# Charger_group2.net
KiCad netlist of a schematic drawn in Altium Designer
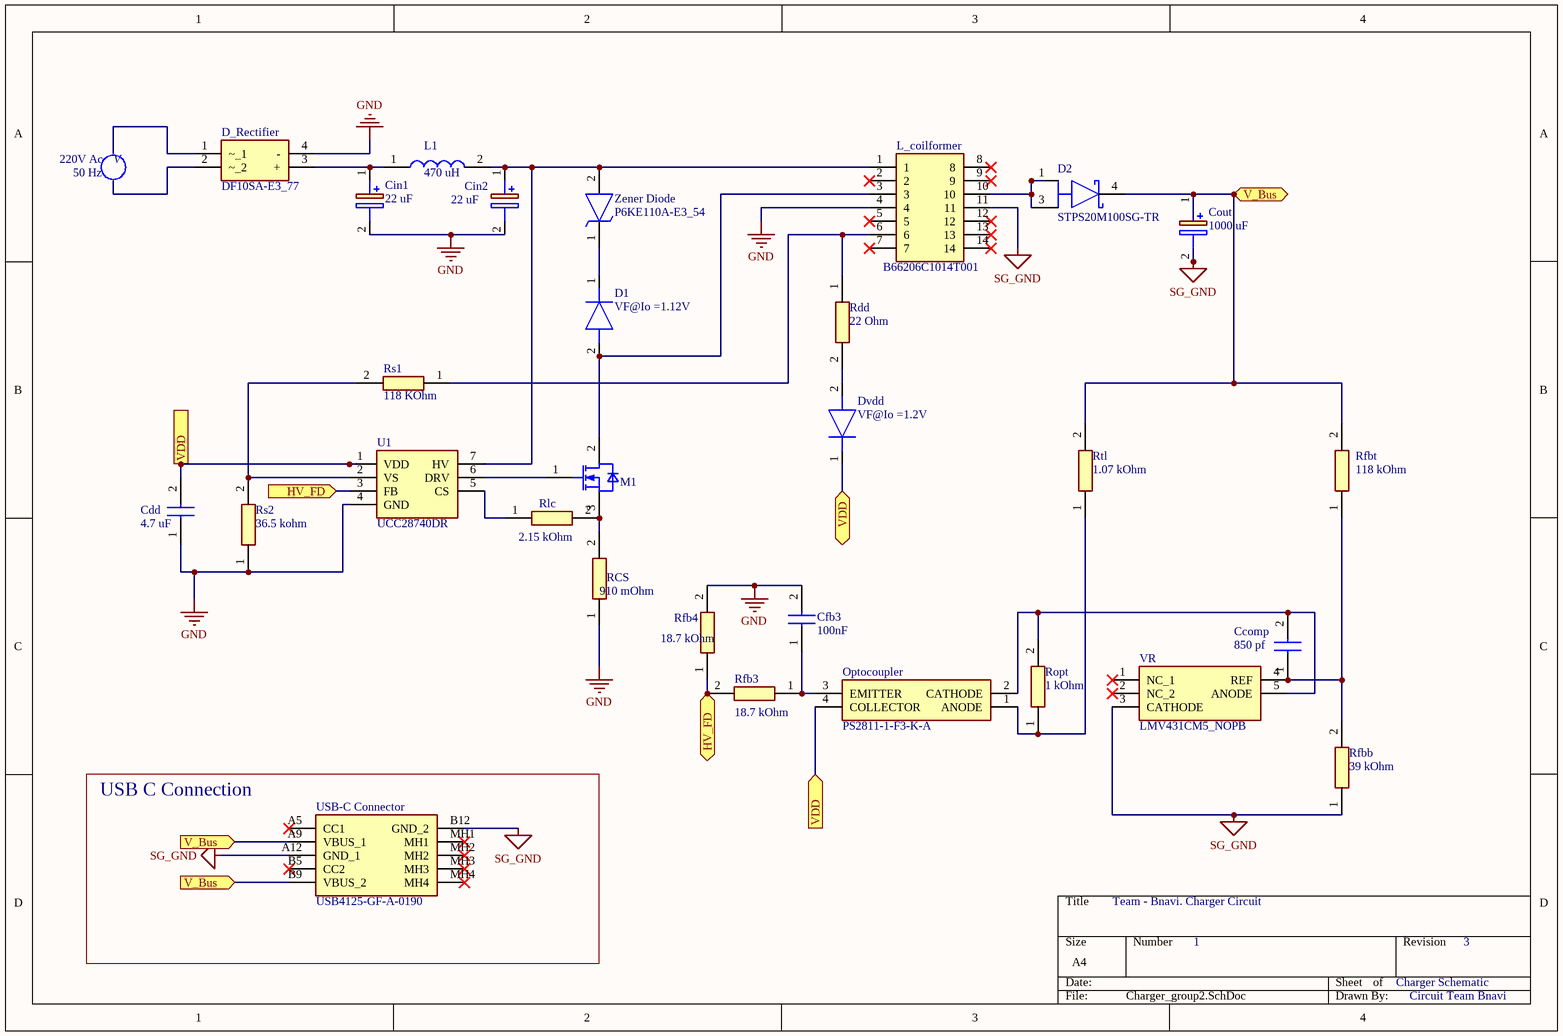
[diagram p0: Charger_group2.SchDoc]

(export (version "E")
  (design (tool "Eeschema 10.0.6"))
  (components
    (comp (ref "Ccomp")
      (value "850 pf")
      (footprint "SamacSys:CAPC1608X90N")
      (description "Capacitor")
      (fields
        (field (name "MANUFACTURER_PART_NUMBER") "06031C851JAT2A")
        (field (name "MOUSER PART NUMBER") "581-06031C851JAT2A")
      )
      (libsource (lib "SamacSys") (part "06031C851JAT2A"))
    )
    (comp (ref "Cdd")
      (value "4.7 uF")
      (footprint "SamacSys:CAPC2012X145N")
      (description "Capacitor")
      (fields
        (field (name "MANUFACTURER_PART_NUMBER") "CGA4J1X7R1V475K125AC")
        (field (name "MOUSER PART NUMBER") "810-CGA4J1X7R1V475KC")
      )
      (libsource (lib "*") (part "CGA4J1X7R1V475K125AC"))
    )
    (comp (ref "Cfb3")
      (value "100nF")
      (footprint "SamacSys:CAPC2013X94N")
      (description "Capacitor")
      (fields
        (field (name "MANUFACTURER_PART_NUMBER") "08053C104JAZ2A")
        (field (name "MOUSER PART NUMBER") "581-08053C104JAZ2A")
      )
      (libsource (lib "SamacSys") (part "08053C104JAZ2A"))
    )
    (comp (ref "Cin1")
      (value "22 uF")
      (footprint "SamacSys:CAPPRD500W60D1275H2200")
      (description "Capacitor Polarised")
      (fields
        (field (name "MANUFACTURER_PART_NUMBER") "400PK22MEFC12.5X20")
        (field (name "MOUSER PART NUMBER") "232-400PK22MEFC125X2")
      )
      (libsource (lib "SamacSys") (part "400PK22MEFC12.5X20"))
    )
    (comp (ref "Cin2")
      (value "22 uF")
      (footprint "SamacSys:CAPPRD500W60D1275H2200")
      (description "Capacitor Polarised")
      (fields
        (field (name "MANUFACTURER_PART_NUMBER") "400PK22MEFC12.5X20")
        (field (name "MOUSER PART NUMBER") "232-400PK22MEFC125X2")
      )
      (libsource (lib "SamacSys") (part "400PK22MEFC12.5X20"))
    )
    (comp (ref "Cout")
      (value "1000 uF")
      (footprint "SamacSys:CAPPRD500W65D1000H2700")
      (description "Capacitor Polarised")
      (fields
        (field (name "MANUFACTURER_PART_NUMBER") "EEU-FC1C102")
        (field (name "MOUSER PART NUMBER") "667-EEU-FC1C102")
      )
      (libsource (lib "*") (part "EEU-FC1C102"))
    )
    (comp (ref "D1")
      (value "VF@Io =1.12V")
      (footprint "SamacSys:DIOM7959X262N")
      (description "Diode")
      (fields
        (field (name "MANUFACTURER_PART_NUMBER") "CD214C-F3600")
        (field (name "MOUSER PART NUMBER") "652-CD214C-F3600")
      )
      (libsource (lib "SamacSys") (part "CD214C-F3600"))
    )
    (comp (ref "D2")
      (value "STPS20M100SG-TR")
      (footprint "FP-STPS20M100SG-TR-MFG")
      (description "DIODE SCHOTTKY 100V 20A D2PAK")
      (fields
        (field (name "MANUFACTURER") "STMicroelectronics")
        (field (name "OCTOPART") "https://octopart.com/stps20m100sg-tr-stmicroelectronics-17669033")
      )
      (libsource (lib "Altium Content Vault") (part "51e2ec8066ff851c79fc2400fdb0e37"))
    )
    (comp (ref "Dvdd")
      (value "VF@Io =1.2V")
      (footprint "SamacSys:DIOM5436X330N")
      (description "Diode")
      (fields
        (field (name "MANUFACTURER_PART_NUMBER") "UFS180Je3/TR13")
        (field (name "MOUSER PART NUMBER") "494-UFS180JE3/TR13")
      )
      (libsource (lib "SamacSys") (part "UFS180Je3_TR13"))
    )
    (comp (ref "D_Rectifier")
      (value "DF10SA-E3_77")
      (footprint "SamacSys:SOP510P1005X330-4N")
      (description "Diode")
      (fields
        (field (name "MANUFACTURER_PART_NUMBER") "DF10SA-E3/77")
        (field (name "MOUSER PART NUMBER") "625-DF10SA-E3")
      )
      (libsource (lib "SamacSys") (part "DF10SA-E3_77"))
    )
    (comp (ref "L1")
      (value "470 uH")
      (footprint "SamacSys:WE-PD2_105455")
      (description "Inductor")
      (fields
        (field (name "MANUFACTURER_PART_NUMBER") "744776247")
        (field (name "MOUSER PART NUMBER") "710-744776247")
      )
      (libsource (lib "SamacSys") (part "744776247"))
    )
    (comp (ref "L_coilformer")
      (value "B66206C1014T001")
      (footprint "SamacSys:B66206C1014T001")
      (description "Inductor")
      (libsource (lib "SamacSys") (part "B66206C1014T001"))
    )
    (comp (ref "M1")
      (value "IPD80R1K0CE")
      (footprint "TO229P994X241-3N:TO229P994X241-3N")
      (description "CoolMos CE 800V Power Transistor")
      (fields (field (name "MANUFACTURER") "Infineon Technologies"))
      (libsource (lib "IPD80R1K0CE") (part "IPD80R1K0CE"))
    )
    (comp (ref "Optocoupler")
      (value "PS2811-1-F3-K-A")
      (footprint "SamacSys:SOIC127P700X210-4N")
      (description "Integrated Circuit")
      (fields (field (name "MOUSER PART NUMBER") "551-PS2811-1-F3-K-A"))
      (libsource (lib "SamacSys") (part "PS2811-1-F3-K-A"))
    )
    (comp (ref "RCS")
      (value "910 mOhm")
      (footprint "SamacSys:RESC2012X60N")
      (description "Resistor")
      (fields
        (field (name "MANUFACTURER_PART_NUMBER") "CRM0805-FX-R910ELF")
        (field (name "MOUSER PART NUMBER") "652-CRM0805FXR910ELF")
      )
      (libsource (lib "SamacSys") (part "CRM0805-FX-R910ELF"))
    )
    (comp (ref "Rdd")
      (value "22 Ohm")
      (footprint "SamacSys:RESC1608X55N")
      (description "Resistor")
      (fields
        (field (name "MANUFACTURER_PART_NUMBER") "RC0603FR-0722RL")
        (field (name "MOUSER PART NUMBER") "603-RC0603FR-0722RL")
      )
      (libsource (lib "SamacSys") (part "RC0603FR-0722RL"))
    )
    (comp (ref "Rfb3")
      (value "18.7 kOhm")
      (footprint "SamacSys:RESC0603X26N")
      (description "Resistor")
      (fields
        (field (name "MANUFACTURER_PART_NUMBER") "RC0201FR-07205KL")
        (field (name "MOUSER PART NUMBER") "603-RC0201FR-07205KL")
      )
      (libsource (lib "SamacSys") (part "RC0201FR-07205KL"))
    )
    (comp (ref "Rfb4")
      (value "18.7 kOhm")
      (footprint "SamacSys:RESC0603X26N")
      (description "Resistor")
      (fields
        (field (name "MANUFACTURER_PART_NUMBER") "RC0201FR-0718K7L")
        (field (name "MOUSER PART NUMBER") "603-RC0201FR-0718K7L")
      )
      (libsource (lib "SamacSys") (part "RC0201FR-0718K7L"))
    )
    (comp (ref "Rfbb")
      (value "39 kOhm")
      (footprint "SamacSys:RESC1608X55N")
      (description "Resistor")
      (fields
        (field (name "MANUFACTURER_PART_NUMBER") "RC0603FR-0739KL")
        (field (name "MOUSER PART NUMBER") "603-RC0603FR-0739KL")
      )
      (libsource (lib "SamacSys") (part "RC0603FR-0739KL"))
    )
    (comp (ref "Rfbt")
      (value "118 kOhm")
      (footprint "SamacSys:RESC1005X40N")
      (description "Resistor")
      (fields
        (field (name "MANUFACTURER_PART_NUMBER") "CRCW0402118KFKED")
        (field (name "MOUSER PART NUMBER") "71-CRCW0402-118K-E3")
      )
      (libsource (lib "") (part "CRCW0402118KFKED_1"))
    )
    (comp (ref "Rlc")
      (value "2.15 kOhm")
      (footprint "SamacSys:RESC1005X40N")
      (description "Resistor")
      (fields
        (field (name "MANUFACTURER_PART_NUMBER") "CRCW04022K15FKED")
        (field (name "MOUSER PART NUMBER") "71-CRCW0402-2.15K-E3")
      )
      (libsource (lib "SamacSys") (part "CRCW04022K15FKED"))
    )
    (comp (ref "Ropt")
      (value "1 kOhm")
      (footprint "SamacSys:RESC1005X40N")
      (description "Resistor")
      (fields
        (field (name "MANUFACTURER_PART_NUMBER") "CRCW04021K00FKEDHP")
        (field (name "MOUSER PART NUMBER") "71-CRCW04021K00FKEDH")
      )
      (libsource (lib "SamacSys") (part "CRCW04021K00FKEDHP"))
    )
    (comp (ref "Rs1")
      (value "118 KOhm")
      (footprint "SamacSys:RESC1005X40N")
      (description "Resistor")
      (fields
        (field (name "MANUFACTURER_PART_NUMBER") "CRCW0402118KFKED")
        (field (name "MOUSER PART NUMBER") "71-CRCW0402-118K-E3")
      )
      (libsource (lib "SamacSys") (part "CRCW0402118KFKED"))
    )
    (comp (ref "Rs2")
      (value "36.5 kohm")
      (footprint "SamacSys:RESC0603X26N")
      (description "Resistor")
      (fields
        (field (name "MANUFACTURER_PART_NUMBER") "RC0201FR-0736K5L")
        (field (name "MOUSER PART NUMBER") "603-RC0201FR-0736K5L")
      )
      (libsource (lib "SamacSys") (part "RC0201FR-0736K5L"))
    )
    (comp (ref "Rtl")
      (value "1.07 kOhm")
      (footprint "SamacSys:RESC1005X40N")
      (description "Resistor")
      (fields
        (field (name "MANUFACTURER_PART_NUMBER") "CRCW04021K07FKED")
        (field (name "MOUSER PART NUMBER") "71-CRCW0402-1.07K-E3")
      )
      (libsource (lib "SamacSys") (part "CRCW04021K07FKED"))
    )
    (comp (ref "U1")
      (value "UCC28740DR")
      (footprint "SamacSys:D(R-PDSO-G7)")
      (description "Inductor")
      (fields (field (name "MOUSER PART NUMBER") "595-UCC28740DR"))
      (libsource (lib "SamacSys") (part "UCC28740DR"))
    )
    (comp (ref "USB-C Connector")
      (value "USB4125-GF-A-0190")
      (footprint "SamacSys:USB4125GFA0190")
      (description "Connector")
      (fields (field (name "MOUSER PART NUMBER") "640-USB4125-GF-A-190"))
      (libsource (lib "*") (part "USB4125-GF-A-0190"))
    )
    (comp (ref "VR")
      (value "LMV431CM5_NOPB")
      (footprint "SamacSys:SOT95P280X145-5N")
      (description "Integrated Circuit")
      (fields
        (field (name "MANUFACTURER_PART_NUMBER") "LMV431CM5/NOPB")
        (field (name "MOUSER PART NUMBER") "926-LMV431CM5/NOPB")
      )
      (libsource (lib "SamacSys") (part "LMV431CM5_NOPB"))
    )
    (comp (ref "Zener Diode")
      (value "P6KE110A-E3_54")
      (footprint "SamacSys:DIOAD1995W86L635D340")
      (description "TVS Diode (Uni-directional)")
      (fields
        (field (name "MANUFACTURER_PART_NUMBER") "P6KE110A-E3/54")
        (field (name "MOUSER PART NUMBER") "625-P6KE110A-E3")
      )
      (libsource (lib "SamacSys") (part "P6KE110A-E3_54"))
    )
  )
  (nets
    (net (code "1") (name "/HV_FD") (class "Default")
      (node (ref "Rfb3") (pin "2") (pinfunction "2_2") (pintype "passive"))
      (node (ref "Rfb4") (pin "1") (pinfunction "1_1") (pintype "passive"))
      (node (ref "U1") (pin "3") (pinfunction "FB_3") (pintype "passive"))
    )
    (net (code "2") (name "/VDD") (class "Default")
      (node (ref "Cdd") (pin "2") (pinfunction "2_2") (pintype "passive"))
      (node (ref "Dvdd") (pin "1") (pinfunction "K_1") (pintype "passive"))
      (node (ref "Optocoupler") (pin "4") (pinfunction "COLLECTOR_4") (pintype "passive"))
      (node (ref "U1") (pin "1") (pinfunction "VDD_1") (pintype "passive"))
    )
    (net (code "3") (name "/V_Bus") (class "Default")
      (node (ref "Cout") (pin "1") (pinfunction "+_1") (pintype "passive"))
      (node (ref "D2") (pin "4") (pinfunction "K_4") (pintype "passive"))
      (node (ref "Rfbt") (pin "2") (pinfunction "2_2") (pintype "passive"))
      (node (ref "Rtl") (pin "2") (pinfunction "2_2") (pintype "passive"))
      (node (ref "USB-C Connector") (pin "A9") (pinfunction "VBUS_1_A9") (pintype "passive"))
      (node (ref "USB-C Connector") (pin "B9") (pinfunction "VBUS_2_B9") (pintype "passive"))
    )
    (net (code "4") (name "GND") (class "Default")
      (node (ref "Cdd") (pin "1") (pinfunction "1_1") (pintype "passive"))
      (node (ref "Cfb3") (pin "2") (pinfunction "C2_2") (pintype "passive"))
      (node (ref "Cin1") (pin "2") (pinfunction "-_2") (pintype "passive"))
      (node (ref "Cin2") (pin "2") (pinfunction "-_2") (pintype "passive"))
      (node (ref "D_Rectifier") (pin "4") (pinfunction "-_4") (pintype "passive"))
      (node (ref "L_coilformer") (pin "4") (pinfunction "4_4") (pintype "passive"))
      (node (ref "RCS") (pin "1") (pinfunction "1_1") (pintype "passive"))
      (node (ref "Rfb4") (pin "2") (pinfunction "2_2") (pintype "passive"))
      (node (ref "Rs2") (pin "1") (pinfunction "1_1") (pintype "passive"))
      (node (ref "U1") (pin "4") (pinfunction "GND_4") (pintype "passive"))
    )
    (net (code "5") (name "Net-(Cfb3-C1)") (class "Default")
      (node (ref "Cfb3") (pin "1") (pinfunction "C1_1") (pintype "passive"))
      (node (ref "Optocoupler") (pin "3") (pinfunction "EMITTER_3") (pintype "passive"))
      (node (ref "Rfb3") (pin "1") (pinfunction "1_1") (pintype "passive"))
    )
    (net (code "6") (name "Net-(Cin1-+)") (class "Default")
      (node (ref "Cin1") (pin "1") (pinfunction "+_1") (pintype "passive"))
      (node (ref "D_Rectifier") (pin "3") (pinfunction "+_3") (pintype "passive"))
      (node (ref "L1") (pin "1") (pinfunction "1_1") (pintype "passive"))
    )
    (net (code "7") (name "Net-(Cin2-+)") (class "Default")
      (node (ref "Cin2") (pin "1") (pinfunction "+_1") (pintype "passive"))
      (node (ref "L1") (pin "2") (pinfunction "2_2") (pintype "passive"))
      (node (ref "L_coilformer") (pin "1") (pinfunction "1_1") (pintype "passive"))
      (node (ref "U1") (pin "7") (pinfunction "HV_7") (pintype "passive"))
      (node (ref "Zener Diode") (pin "2") (pinfunction "A_2") (pintype "passive"))
    )
    (net (code "8") (name "Net-(D1-A)") (class "Default")
      (node (ref "D1") (pin "2") (pinfunction "A_2") (pintype "passive"))
      (node (ref "L_coilformer") (pin "3") (pinfunction "3_3") (pintype "passive"))
      (node (ref "M1") (pin "2") (pinfunction "DRAIN_2") (pintype "passive"))
    )
    (net (code "9") (name "Net-(D1-K)") (class "Default")
      (node (ref "D1") (pin "1") (pinfunction "K_1") (pintype "passive"))
      (node (ref "Zener Diode") (pin "1") (pinfunction "K_1") (pintype "passive"))
    )
    (net (code "10") (name "Net-(D2-A-Pad1)") (class "Default")
      (node (ref "D2") (pin "1") (pinfunction "A_1") (pintype "passive"))
      (node (ref "D2") (pin "3") (pinfunction "A_3") (pintype "passive"))
      (node (ref "L_coilformer") (pin "10") (pinfunction "10_10") (pintype "passive"))
    )
    (net (code "11") (name "Net-(Dvdd-A)") (class "Default")
      (node (ref "Dvdd") (pin "2") (pinfunction "A_2") (pintype "passive"))
      (node (ref "Rdd") (pin "2") (pinfunction "2_2") (pintype "passive"))
    )
    (net (code "12") (name "Net-(L_coilformer-Pad6)") (class "Default")
      (node (ref "L_coilformer") (pin "6") (pinfunction "6_6") (pintype "passive"))
      (node (ref "Rdd") (pin "1") (pinfunction "1_1") (pintype "passive"))
      (node (ref "Rs1") (pin "1") (pinfunction "1_1") (pintype "passive"))
    )
    (net (code "13") (name "Net-(M1-GATE)") (class "Default")
      (node (ref "M1") (pin "1") (pinfunction "GATE_1") (pintype "passive"))
      (node (ref "U1") (pin "6") (pinfunction "DRV_6") (pintype "passive"))
    )
    (net (code "14") (name "Net-(M1-SOURCE)") (class "Default")
      (node (ref "M1") (pin "3") (pinfunction "SOURCE_3") (pintype "passive"))
      (node (ref "RCS") (pin "2") (pinfunction "2_2") (pintype "passive"))
      (node (ref "Rlc") (pin "2") (pinfunction "2_2") (pintype "passive"))
    )
    (net (code "15") (name "Net-(Optocoupler-ANODE)") (class "Default")
      (node (ref "Optocoupler") (pin "1") (pinfunction "ANODE_1") (pintype "passive"))
      (node (ref "Ropt") (pin "1") (pinfunction "1_1") (pintype "passive"))
      (node (ref "Rtl") (pin "1") (pinfunction "1_1") (pintype "passive"))
    )
    (net (code "16") (name "Net-(Optocoupler-CATHODE)") (class "Default")
      (node (ref "Ccomp") (pin "2") (pinfunction "2_2") (pintype "passive"))
      (node (ref "Optocoupler") (pin "2") (pinfunction "CATHODE_2") (pintype "passive"))
      (node (ref "Ropt") (pin "2") (pinfunction "2_2") (pintype "passive"))
      (node (ref "VR") (pin "5") (pinfunction "ANODE_5") (pintype "passive"))
    )
    (net (code "17") (name "Net-(U1-CS)") (class "Default")
      (node (ref "Rlc") (pin "1") (pinfunction "1_1") (pintype "passive"))
      (node (ref "U1") (pin "5") (pinfunction "CS_5") (pintype "passive"))
    )
    (net (code "18") (name "Net-(U1-VS)") (class "Default")
      (node (ref "Rs1") (pin "2") (pinfunction "2_2") (pintype "passive"))
      (node (ref "Rs2") (pin "2") (pinfunction "2_2") (pintype "passive"))
      (node (ref "U1") (pin "2") (pinfunction "VS_2") (pintype "passive"))
    )
    (net (code "19") (name "Net-(VR-REF)") (class "Default")
      (node (ref "Ccomp") (pin "1") (pinfunction "1_1") (pintype "passive"))
      (node (ref "Rfbb") (pin "2") (pinfunction "2_2") (pintype "passive"))
      (node (ref "Rfbt") (pin "1") (pinfunction "1_1") (pintype "passive"))
      (node (ref "VR") (pin "4") (pinfunction "REF_4") (pintype "passive"))
    )
    (net (code "20") (name "SG_GND") (class "Default")
      (node (ref "Cout") (pin "2") (pinfunction "-_2") (pintype "passive"))
      (node (ref "L_coilformer") (pin "11") (pinfunction "11_11") (pintype "passive"))
      (node (ref "Rfbb") (pin "1") (pinfunction "1_1") (pintype "passive"))
      (node (ref "USB-C Connector") (pin "A12") (pinfunction "GND_1_A12") (pintype "passive"))
      (node (ref "USB-C Connector") (pin "B12") (pinfunction "GND_2_B12") (pintype "passive"))
      (node (ref "VR") (pin "3") (pinfunction "CATHODE_3") (pintype "passive"))
    )
    (net (code "21") (name "unconnected-(D_Rectifier-~_1-Pad1)") (class "Default")
      (node (ref "D_Rectifier") (pin "1") (pinfunction "~_1_1") (pintype "passive"))
    )
    (net (code "22") (name "unconnected-(D_Rectifier-~_2-Pad2)") (class "Default")
      (node (ref "D_Rectifier") (pin "2") (pinfunction "~_2_2") (pintype "passive"))
    )
    (net (code "23") (name "unconnected-(L_coilformer-Pad2)") (class "Default")
      (node (ref "L_coilformer") (pin "2") (pinfunction "2_2") (pintype "passive+no_connect"))
    )
    (net (code "24") (name "unconnected-(L_coilformer-Pad5)") (class "Default")
      (node (ref "L_coilformer") (pin "5") (pinfunction "5_5") (pintype "passive+no_connect"))
    )
    (net (code "25") (name "unconnected-(L_coilformer-Pad7)") (class "Default")
      (node (ref "L_coilformer") (pin "7") (pinfunction "7_7") (pintype "passive+no_connect"))
    )
    (net (code "26") (name "unconnected-(L_coilformer-Pad8)") (class "Default")
      (node (ref "L_coilformer") (pin "8") (pinfunction "8_8") (pintype "passive+no_connect"))
    )
    (net (code "27") (name "unconnected-(L_coilformer-Pad9)") (class "Default")
      (node (ref "L_coilformer") (pin "9") (pinfunction "9_9") (pintype "passive+no_connect"))
    )
    (net (code "28") (name "unconnected-(L_coilformer-Pad12)") (class "Default")
      (node (ref "L_coilformer") (pin "12") (pinfunction "12_12") (pintype "passive+no_connect"))
    )
    (net (code "29") (name "unconnected-(L_coilformer-Pad13)") (class "Default")
      (node (ref "L_coilformer") (pin "13") (pinfunction "13_13") (pintype "passive+no_connect"))
    )
    (net (code "30") (name "unconnected-(L_coilformer-Pad14)") (class "Default")
      (node (ref "L_coilformer") (pin "14") (pinfunction "14_14") (pintype "passive+no_connect"))
    )
    (net (code "31") (name "unconnected-(USB-C Connector-CC1-PadA5)") (class "Default")
      (node (ref "USB-C Connector") (pin "A5") (pinfunction "CC1_A5") (pintype "passive+no_connect"))
    )
    (net (code "32") (name "unconnected-(USB-C Connector-CC2-PadB5)") (class "Default")
      (node (ref "USB-C Connector") (pin "B5") (pinfunction "CC2_B5") (pintype "passive+no_connect"))
    )
    (net (code "33") (name "unconnected-(USB-C Connector-PadMH1)") (class "Default")
      (node (ref "USB-C Connector") (pin "MH1") (pinfunction "MH1_MH1") (pintype "passive+no_connect"))
    )
    (net (code "34") (name "unconnected-(USB-C Connector-PadMH2)") (class "Default")
      (node (ref "USB-C Connector") (pin "MH2") (pinfunction "MH2_MH2") (pintype "passive+no_connect"))
    )
    (net (code "35") (name "unconnected-(USB-C Connector-PadMH3)") (class "Default")
      (node (ref "USB-C Connector") (pin "MH3") (pinfunction "MH3_MH3") (pintype "passive+no_connect"))
    )
    (net (code "36") (name "unconnected-(USB-C Connector-PadMH4)") (class "Default")
      (node (ref "USB-C Connector") (pin "MH4") (pinfunction "MH4_MH4") (pintype "passive+no_connect"))
    )
    (net (code "37") (name "unconnected-(VR-NC_1-Pad1)") (class "Default")
      (node (ref "VR") (pin "1") (pinfunction "NC_1_1") (pintype "passive+no_connect"))
    )
    (net (code "38") (name "unconnected-(VR-NC_2-Pad2)") (class "Default")
      (node (ref "VR") (pin "2") (pinfunction "NC_2_2") (pintype "passive+no_connect"))
    )
  )
)
